# CPU_-_LCD.net
KiCad netlist of a schematic drawn in Altium Designer
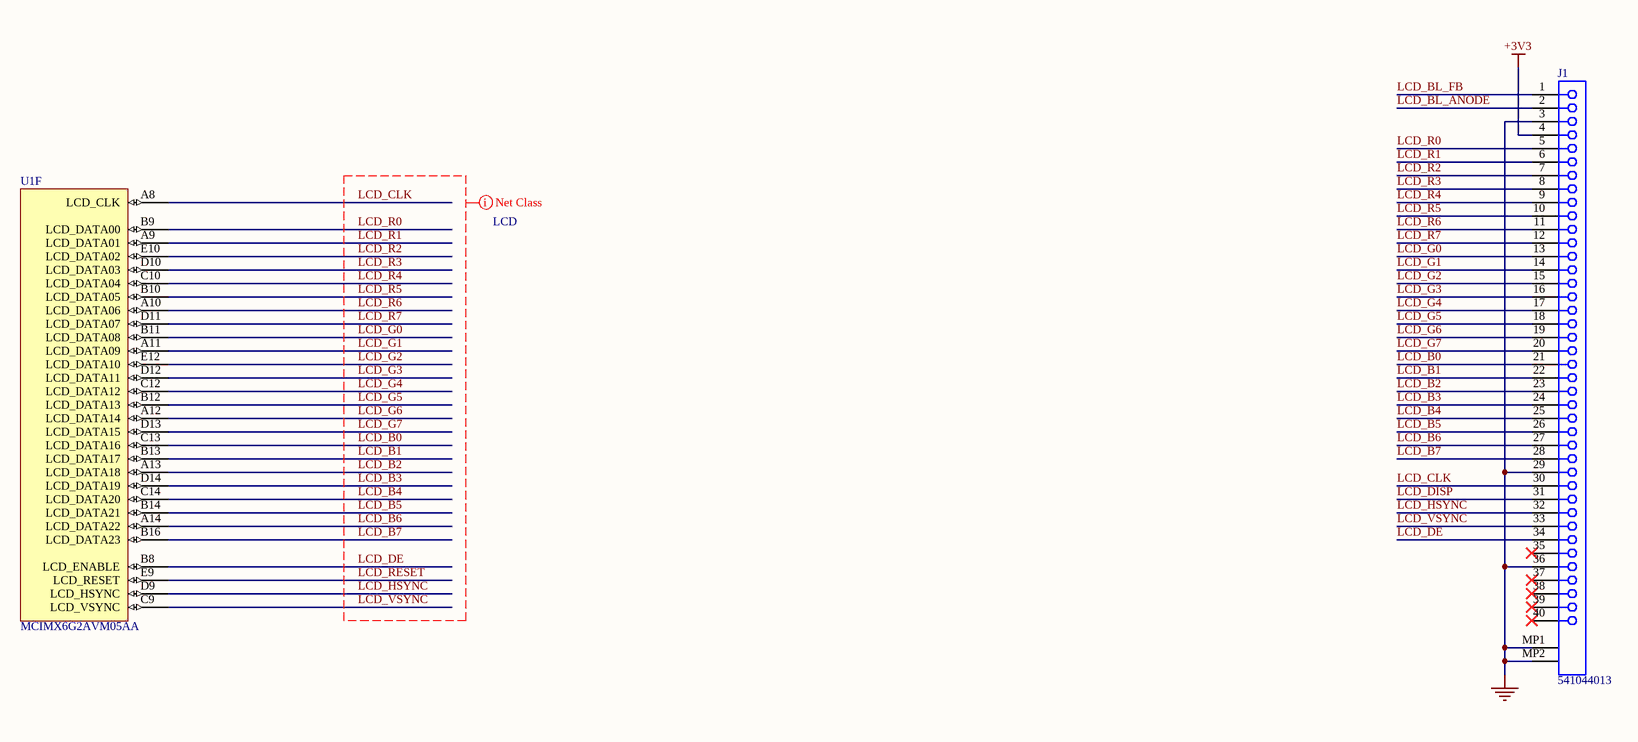
[diagram p0: CPU - LCD.SchDoc]

(export (version "E")
  (design (tool "Eeschema 10.0.6"))
  (components
    (comp (ref "J1")
      (value "541044013")
      (footprint "MOLX-54104-4031")
      (libsource (lib "Connectors") (part "MOLX-54104-4031"))
    )
    (comp (ref "U1")
      (value "MCIMX6G2AVM05AA")
      (footprint "BGA289C80P17X17_1400X1400X132")
      (libsource (lib "Hub-UV17") (part "MCIMX6G2AVM05AA"))
    )
  )
  (nets
    (net (code "1") (name "+3V3") (class "Default")
      (node (ref "J1") (pin "4") (pinfunction "4_4") (pintype "passive"))
    )
    (net (code "2") (name "/LCD_B0") (class "Default")
      (node (ref "J1") (pin "21") (pinfunction "21_21") (pintype "passive"))
      (node (ref "U1") (pin "C13") (pinfunction "LCD_DATA16_C13") (pintype "bidirectional"))
    )
    (net (code "3") (name "/LCD_B1") (class "Default")
      (node (ref "J1") (pin "22") (pinfunction "22_22") (pintype "passive"))
      (node (ref "U1") (pin "B13") (pinfunction "LCD_DATA17_B13") (pintype "bidirectional"))
    )
    (net (code "4") (name "/LCD_B2") (class "Default")
      (node (ref "J1") (pin "23") (pinfunction "23_23") (pintype "passive"))
      (node (ref "U1") (pin "A13") (pinfunction "LCD_DATA18_A13") (pintype "bidirectional"))
    )
    (net (code "5") (name "/LCD_B3") (class "Default")
      (node (ref "J1") (pin "24") (pinfunction "24_24") (pintype "passive"))
      (node (ref "U1") (pin "D14") (pinfunction "LCD_DATA19_D14") (pintype "bidirectional"))
    )
    (net (code "6") (name "/LCD_B4") (class "Default")
      (node (ref "J1") (pin "25") (pinfunction "25_25") (pintype "passive"))
      (node (ref "U1") (pin "C14") (pinfunction "LCD_DATA20_C14") (pintype "bidirectional"))
    )
    (net (code "7") (name "/LCD_B5") (class "Default")
      (node (ref "J1") (pin "26") (pinfunction "26_26") (pintype "passive"))
      (node (ref "U1") (pin "B14") (pinfunction "LCD_DATA21_B14") (pintype "bidirectional"))
    )
    (net (code "8") (name "/LCD_B6") (class "Default")
      (node (ref "J1") (pin "27") (pinfunction "27_27") (pintype "passive"))
      (node (ref "U1") (pin "A14") (pinfunction "LCD_DATA22_A14") (pintype "bidirectional"))
    )
    (net (code "9") (name "/LCD_B7") (class "Default")
      (node (ref "J1") (pin "28") (pinfunction "28_28") (pintype "passive"))
      (node (ref "U1") (pin "B16") (pinfunction "LCD_DATA23_B16") (pintype "bidirectional"))
    )
    (net (code "10") (name "/LCD_BL_ANODE") (class "Default")
      (node (ref "J1") (pin "2") (pinfunction "2_2") (pintype "passive"))
    )
    (net (code "11") (name "/LCD_BL_FB") (class "Default")
      (node (ref "J1") (pin "1") (pinfunction "1_1") (pintype "passive"))
    )
    (net (code "12") (name "/LCD_CLK") (class "Default")
      (node (ref "J1") (pin "30") (pinfunction "30_30") (pintype "passive"))
      (node (ref "U1") (pin "A8") (pinfunction "LCD_CLK_A8") (pintype "bidirectional"))
    )
    (net (code "13") (name "/LCD_DE") (class "Default")
      (node (ref "J1") (pin "34") (pinfunction "34_34") (pintype "passive"))
      (node (ref "U1") (pin "B8") (pinfunction "LCD_ENABLE_B8") (pintype "bidirectional"))
    )
    (net (code "14") (name "/LCD_DISP") (class "Default")
      (node (ref "J1") (pin "31") (pinfunction "31_31") (pintype "passive"))
    )
    (net (code "15") (name "/LCD_G0") (class "Default")
      (node (ref "J1") (pin "13") (pinfunction "13_13") (pintype "passive"))
      (node (ref "U1") (pin "B11") (pinfunction "LCD_DATA08_B11") (pintype "bidirectional"))
    )
    (net (code "16") (name "/LCD_G1") (class "Default")
      (node (ref "J1") (pin "14") (pinfunction "14_14") (pintype "passive"))
      (node (ref "U1") (pin "A11") (pinfunction "LCD_DATA09_A11") (pintype "bidirectional"))
    )
    (net (code "17") (name "/LCD_G2") (class "Default")
      (node (ref "J1") (pin "15") (pinfunction "15_15") (pintype "passive"))
      (node (ref "U1") (pin "E12") (pinfunction "LCD_DATA10_E12") (pintype "bidirectional"))
    )
    (net (code "18") (name "/LCD_G3") (class "Default")
      (node (ref "J1") (pin "16") (pinfunction "16_16") (pintype "passive"))
      (node (ref "U1") (pin "D12") (pinfunction "LCD_DATA11_D12") (pintype "bidirectional"))
    )
    (net (code "19") (name "/LCD_G4") (class "Default")
      (node (ref "J1") (pin "17") (pinfunction "17_17") (pintype "passive"))
      (node (ref "U1") (pin "C12") (pinfunction "LCD_DATA12_C12") (pintype "bidirectional"))
    )
    (net (code "20") (name "/LCD_G5") (class "Default")
      (node (ref "J1") (pin "18") (pinfunction "18_18") (pintype "passive"))
      (node (ref "U1") (pin "B12") (pinfunction "LCD_DATA13_B12") (pintype "bidirectional"))
    )
    (net (code "21") (name "/LCD_G6") (class "Default")
      (node (ref "J1") (pin "19") (pinfunction "19_19") (pintype "passive"))
      (node (ref "U1") (pin "A12") (pinfunction "LCD_DATA14_A12") (pintype "bidirectional"))
    )
    (net (code "22") (name "/LCD_G7") (class "Default")
      (node (ref "J1") (pin "20") (pinfunction "20_20") (pintype "passive"))
      (node (ref "U1") (pin "D13") (pinfunction "LCD_DATA15_D13") (pintype "bidirectional"))
    )
    (net (code "23") (name "/LCD_HSYNC") (class "Default")
      (node (ref "J1") (pin "32") (pinfunction "32_32") (pintype "passive"))
      (node (ref "U1") (pin "D9") (pinfunction "LCD_HSYNC_D9") (pintype "bidirectional"))
    )
    (net (code "24") (name "/LCD_R0") (class "Default")
      (node (ref "J1") (pin "5") (pinfunction "5_5") (pintype "passive"))
      (node (ref "U1") (pin "B9") (pinfunction "LCD_DATA00_B9") (pintype "bidirectional"))
    )
    (net (code "25") (name "/LCD_R1") (class "Default")
      (node (ref "J1") (pin "6") (pinfunction "6_6") (pintype "passive"))
      (node (ref "U1") (pin "A9") (pinfunction "LCD_DATA01_A9") (pintype "bidirectional"))
    )
    (net (code "26") (name "/LCD_R2") (class "Default")
      (node (ref "J1") (pin "7") (pinfunction "7_7") (pintype "passive"))
      (node (ref "U1") (pin "E10") (pinfunction "LCD_DATA02_E10") (pintype "bidirectional"))
    )
    (net (code "27") (name "/LCD_R3") (class "Default")
      (node (ref "J1") (pin "8") (pinfunction "8_8") (pintype "passive"))
      (node (ref "U1") (pin "D10") (pinfunction "LCD_DATA03_D10") (pintype "bidirectional"))
    )
    (net (code "28") (name "/LCD_R4") (class "Default")
      (node (ref "J1") (pin "9") (pinfunction "9_9") (pintype "passive"))
      (node (ref "U1") (pin "C10") (pinfunction "LCD_DATA04_C10") (pintype "bidirectional"))
    )
    (net (code "29") (name "/LCD_R5") (class "Default")
      (node (ref "J1") (pin "10") (pinfunction "10_10") (pintype "passive"))
      (node (ref "U1") (pin "B10") (pinfunction "LCD_DATA05_B10") (pintype "bidirectional"))
    )
    (net (code "30") (name "/LCD_R6") (class "Default")
      (node (ref "J1") (pin "11") (pinfunction "11_11") (pintype "passive"))
      (node (ref "U1") (pin "A10") (pinfunction "LCD_DATA06_A10") (pintype "bidirectional"))
    )
    (net (code "31") (name "/LCD_R7") (class "Default")
      (node (ref "J1") (pin "12") (pinfunction "12_12") (pintype "passive"))
      (node (ref "U1") (pin "D11") (pinfunction "LCD_DATA07_D11") (pintype "bidirectional"))
    )
    (net (code "32") (name "/LCD_RESET") (class "Default")
      (node (ref "U1") (pin "E9") (pinfunction "LCD_RESET_E9") (pintype "bidirectional"))
    )
    (net (code "33") (name "/LCD_VSYNC") (class "Default")
      (node (ref "J1") (pin "33") (pinfunction "33_33") (pintype "passive"))
      (node (ref "U1") (pin "C9") (pinfunction "LCD_VSYNC_C9") (pintype "bidirectional"))
    )
    (net (code "34") (name "GND") (class "Default")
      (node (ref "J1") (pin "29") (pinfunction "29_29") (pintype "passive"))
      (node (ref "J1") (pin "3") (pinfunction "3_3") (pintype "passive"))
      (node (ref "J1") (pin "36") (pinfunction "36_36") (pintype "passive"))
      (node (ref "J1") (pin "MP1") (pinfunction "MP1_MP1") (pintype "passive"))
      (node (ref "J1") (pin "MP2") (pinfunction "MP2_MP2") (pintype "passive"))
    )
    (net (code "35") (name "unconnected-(J1-Pad35)") (class "Default")
      (node (ref "J1") (pin "35") (pinfunction "35_35") (pintype "passive+no_connect"))
    )
    (net (code "36") (name "unconnected-(J1-Pad37)") (class "Default")
      (node (ref "J1") (pin "37") (pinfunction "37_37") (pintype "passive+no_connect"))
    )
    (net (code "37") (name "unconnected-(J1-Pad38)") (class "Default")
      (node (ref "J1") (pin "38") (pinfunction "38_38") (pintype "passive+no_connect"))
    )
    (net (code "38") (name "unconnected-(J1-Pad39)") (class "Default")
      (node (ref "J1") (pin "39") (pinfunction "39_39") (pintype "passive+no_connect"))
    )
    (net (code "39") (name "unconnected-(J1-Pad40)") (class "Default")
      (node (ref "J1") (pin "40") (pinfunction "40_40") (pintype "passive+no_connect"))
    )
  )
)
